# HelpDuinoShiled.net
KiCad netlist of a schematic drawn in EAGLE
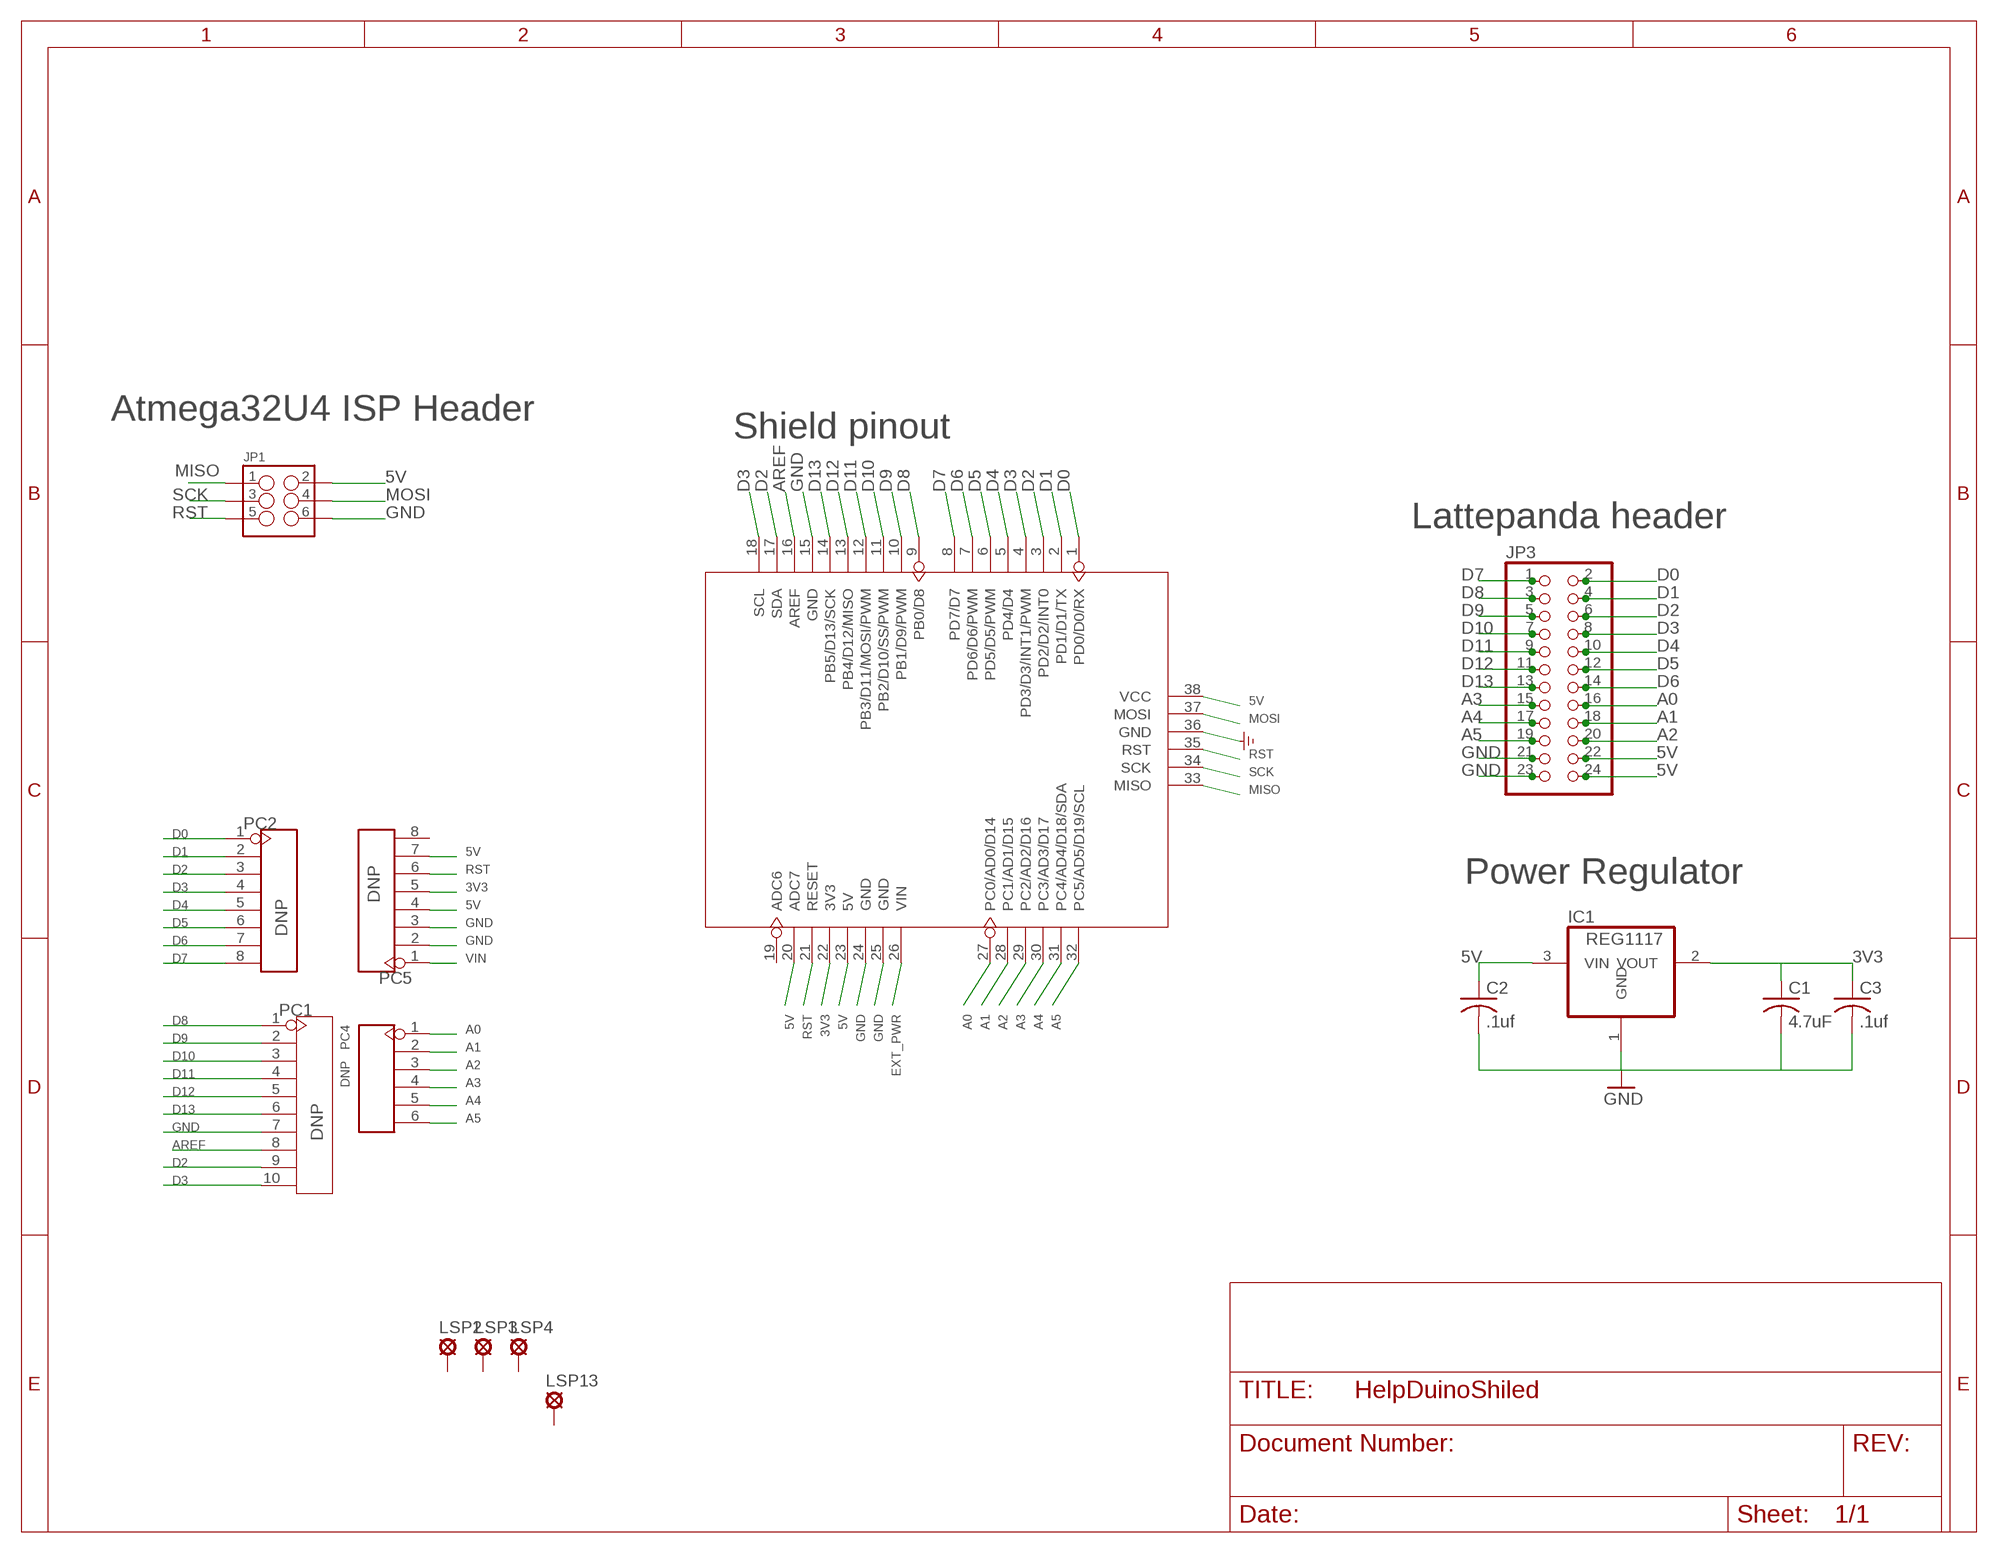
[diagram p0: schematic, sheet 1]

(export (version "E")
  (design (tool "Eeschema 10.0.6"))
  (components
    (comp (ref "C1")
      (value "4.7uF")
      (footprint "eagle-import:C0603K")
      (libsource (lib "eagle-import") (part "C-USC0603K"))
    )
    (comp (ref "C2")
      (value ".1uf")
      (footprint "eagle-import:C0603K")
      (libsource (lib "eagle-import") (part "C-USC0603K"))
    )
    (comp (ref "C3")
      (value ".1uf")
      (footprint "eagle-import:C0603K")
      (libsource (lib "eagle-import") (part "C-USC0603K"))
    )
    (comp (ref "IC1")
      (value "REG1117")
      (footprint "eagle-import:SOT223")
      (libsource (lib "eagle-import") (part "REG1117"))
    )
    (comp (ref "JP1")
      (value "M03X2NO_SILK")
      (footprint "eagle-import:2X3-NS")
      (libsource (lib "eagle-import") (part "M03X2NO_SILK"))
    )
    (comp (ref "JP3")
      (value "PINHD-2X12")
      (footprint "eagle-import:2X12")
      (libsource (lib "eagle-import") (part "PINHD-2X12"))
    )
    (comp (ref "LSP2")
      (value "SE13")
      (footprint "eagle-import:SE13")
      (libsource (lib "eagle-import") (part "SE13"))
    )
    (comp (ref "LSP3")
      (value "SE13")
      (footprint "eagle-import:SE13")
      (libsource (lib "eagle-import") (part "SE13"))
    )
    (comp (ref "LSP4")
      (value "SE13")
      (footprint "eagle-import:SE13")
      (libsource (lib "eagle-import") (part "SE13"))
    )
    (comp (ref "LSP13")
      (value "SE13")
      (footprint "eagle-import:SE13")
      (libsource (lib "eagle-import") (part "SE13"))
    )
    (comp (ref "PC1")
      (value "DNP")
      (footprint "eagle-import:10P-2.54")
      (libsource (lib "eagle-import") (part "HEADER-10P-2.54"))
    )
    (comp (ref "PC2")
      (value "DNP")
      (footprint "eagle-import:8P-2.54")
      (libsource (lib "eagle-import") (part "HEADER-8P-2.54"))
    )
    (comp (ref "PC4")
      (value "DNP")
      (footprint "eagle-import:6P-2.54-65_35MIL")
      (libsource (lib "eagle-import") (part "HEADER-6P-65/35MIL"))
    )
    (comp (ref "PC5")
      (value "DNP")
      (footprint "eagle-import:8P-2.54")
      (libsource (lib "eagle-import") (part "HEADER-8P-2.54"))
    )
    (comp (ref "U1")
      (value "ARDUINO-38PWITH/-SILK")
      (footprint "eagle-import:ARDUINO-38P-WITH_-SILK-500519002")
      (libsource (lib "eagle-import") (part "ARDUINO-38PWITH/-SILK"))
    )
  )
  (nets
    (net (code "1") (name "/3V3") (class "Default")
      (node (ref "C1") (pin "1") (pinfunction "1_1") (pintype "passive"))
      (node (ref "C3") (pin "1") (pinfunction "1_1") (pintype "passive"))
      (node (ref "IC1") (pin "2") (pinfunction "VOUT_2") (pintype "output"))
      (node (ref "PC5") (pin "5") (pinfunction "5_5") (pintype "bidirectional"))
      (node (ref "U1") (pin "22") (pinfunction "3V3_22") (pintype "bidirectional"))
    )
    (net (code "2") (name "/5V") (class "Default")
      (node (ref "C2") (pin "1") (pinfunction "1_1") (pintype "passive"))
      (node (ref "IC1") (pin "3") (pinfunction "VIN_3") (pintype "input"))
      (node (ref "JP1") (pin "2") (pinfunction "2_2") (pintype "bidirectional"))
      (node (ref "JP3") (pin "22") (pinfunction "22_22") (pintype "passive"))
      (node (ref "JP3") (pin "24") (pinfunction "24_24") (pintype "passive"))
      (node (ref "PC5") (pin "4") (pinfunction "4_4") (pintype "bidirectional"))
      (node (ref "PC5") (pin "7") (pinfunction "7_7") (pintype "bidirectional"))
      (node (ref "U1") (pin "20") (pinfunction "ADC7_20") (pintype "bidirectional"))
      (node (ref "U1") (pin "23") (pinfunction "5V_23") (pintype "bidirectional"))
      (node (ref "U1") (pin "38") (pinfunction "VCC_38") (pintype "bidirectional"))
    )
    (net (code "3") (name "/A0") (class "Default")
      (node (ref "JP3") (pin "16") (pinfunction "16_16") (pintype "passive"))
      (node (ref "PC4") (pin "1") (pinfunction "1_1") (pintype "bidirectional"))
      (node (ref "U1") (pin "27") (pinfunction "PC0/AD0/D14_27") (pintype "bidirectional"))
    )
    (net (code "4") (name "/A1") (class "Default")
      (node (ref "JP3") (pin "18") (pinfunction "18_18") (pintype "passive"))
      (node (ref "PC4") (pin "2") (pinfunction "2_2") (pintype "bidirectional"))
      (node (ref "U1") (pin "28") (pinfunction "PC1/AD1/D15_28") (pintype "bidirectional"))
    )
    (net (code "5") (name "/A2") (class "Default")
      (node (ref "JP3") (pin "20") (pinfunction "20_20") (pintype "passive"))
      (node (ref "PC4") (pin "3") (pinfunction "3_3") (pintype "bidirectional"))
      (node (ref "U1") (pin "29") (pinfunction "PC2/AD2/D16_29") (pintype "bidirectional"))
    )
    (net (code "6") (name "/A3") (class "Default")
      (node (ref "JP3") (pin "15") (pinfunction "15_15") (pintype "passive"))
      (node (ref "PC4") (pin "4") (pinfunction "4_4") (pintype "bidirectional"))
      (node (ref "U1") (pin "30") (pinfunction "PC3/AD3/D17_30") (pintype "bidirectional"))
    )
    (net (code "7") (name "/A4") (class "Default")
      (node (ref "JP3") (pin "17") (pinfunction "17_17") (pintype "passive"))
      (node (ref "PC4") (pin "5") (pinfunction "5_5") (pintype "bidirectional"))
      (node (ref "U1") (pin "31") (pinfunction "PC4/AD4/D18/SDA_31") (pintype "bidirectional"))
    )
    (net (code "8") (name "/A5") (class "Default")
      (node (ref "JP3") (pin "19") (pinfunction "19_19") (pintype "passive"))
      (node (ref "PC4") (pin "6") (pinfunction "6_6") (pintype "bidirectional"))
      (node (ref "U1") (pin "32") (pinfunction "PC5/AD5/D19/SCL_32") (pintype "bidirectional"))
    )
    (net (code "9") (name "/AREF") (class "Default")
      (node (ref "PC1") (pin "8") (pinfunction "8_8") (pintype "bidirectional"))
      (node (ref "U1") (pin "16") (pinfunction "AREF_16") (pintype "bidirectional"))
    )
    (net (code "10") (name "/D0") (class "Default")
      (node (ref "JP3") (pin "2") (pinfunction "2_2") (pintype "passive"))
      (node (ref "PC2") (pin "1") (pinfunction "1_1") (pintype "bidirectional"))
      (node (ref "U1") (pin "1") (pinfunction "PD0/D0/RX_1") (pintype "bidirectional"))
    )
    (net (code "11") (name "/D1") (class "Default")
      (node (ref "JP3") (pin "4") (pinfunction "4_4") (pintype "passive"))
      (node (ref "PC2") (pin "2") (pinfunction "2_2") (pintype "bidirectional"))
      (node (ref "U1") (pin "2") (pinfunction "PD1/D1/TX_2") (pintype "bidirectional"))
    )
    (net (code "12") (name "/D2") (class "Default")
      (node (ref "JP3") (pin "6") (pinfunction "6_6") (pintype "passive"))
      (node (ref "PC1") (pin "9") (pinfunction "9_9") (pintype "bidirectional"))
      (node (ref "PC2") (pin "3") (pinfunction "3_3") (pintype "bidirectional"))
      (node (ref "U1") (pin "17") (pinfunction "SDA_17") (pintype "bidirectional"))
      (node (ref "U1") (pin "3") (pinfunction "PD2/D2/INT0_3") (pintype "bidirectional"))
    )
    (net (code "13") (name "/D3") (class "Default")
      (node (ref "JP3") (pin "8") (pinfunction "8_8") (pintype "passive"))
      (node (ref "PC1") (pin "10") (pinfunction "10_10") (pintype "bidirectional"))
      (node (ref "PC2") (pin "4") (pinfunction "4_4") (pintype "bidirectional"))
      (node (ref "U1") (pin "18") (pinfunction "SCL_18") (pintype "bidirectional"))
      (node (ref "U1") (pin "4") (pinfunction "PD3/D3/INT1/PWM_4") (pintype "bidirectional"))
    )
    (net (code "14") (name "/D4") (class "Default")
      (node (ref "JP3") (pin "10") (pinfunction "10_10") (pintype "passive"))
      (node (ref "PC2") (pin "5") (pinfunction "5_5") (pintype "bidirectional"))
      (node (ref "U1") (pin "5") (pinfunction "PD4/D4_5") (pintype "bidirectional"))
    )
    (net (code "15") (name "/D5") (class "Default")
      (node (ref "JP3") (pin "12") (pinfunction "12_12") (pintype "passive"))
      (node (ref "PC2") (pin "6") (pinfunction "6_6") (pintype "bidirectional"))
      (node (ref "U1") (pin "6") (pinfunction "PD5/D5/PWM_6") (pintype "bidirectional"))
    )
    (net (code "16") (name "/D6") (class "Default")
      (node (ref "JP3") (pin "14") (pinfunction "14_14") (pintype "passive"))
      (node (ref "PC2") (pin "7") (pinfunction "7_7") (pintype "bidirectional"))
      (node (ref "U1") (pin "7") (pinfunction "PD6/D6/PWM_7") (pintype "bidirectional"))
    )
    (net (code "17") (name "/D7") (class "Default")
      (node (ref "JP3") (pin "1") (pinfunction "1_1") (pintype "passive"))
      (node (ref "PC2") (pin "8") (pinfunction "8_8") (pintype "bidirectional"))
      (node (ref "U1") (pin "8") (pinfunction "PD7/D7_8") (pintype "bidirectional"))
    )
    (net (code "18") (name "/D8") (class "Default")
      (node (ref "JP3") (pin "3") (pinfunction "3_3") (pintype "passive"))
      (node (ref "PC1") (pin "1") (pinfunction "1_1") (pintype "bidirectional"))
      (node (ref "U1") (pin "9") (pinfunction "PB0/D8_9") (pintype "bidirectional"))
    )
    (net (code "19") (name "/D9") (class "Default")
      (node (ref "JP3") (pin "5") (pinfunction "5_5") (pintype "passive"))
      (node (ref "PC1") (pin "2") (pinfunction "2_2") (pintype "bidirectional"))
      (node (ref "U1") (pin "10") (pinfunction "PB1/D9/PWM_10") (pintype "bidirectional"))
    )
    (net (code "20") (name "/D10") (class "Default")
      (node (ref "JP3") (pin "7") (pinfunction "7_7") (pintype "passive"))
      (node (ref "PC1") (pin "3") (pinfunction "3_3") (pintype "bidirectional"))
      (node (ref "U1") (pin "11") (pinfunction "PB2/D10/SS/PWM_11") (pintype "bidirectional"))
    )
    (net (code "21") (name "/D11") (class "Default")
      (node (ref "JP3") (pin "9") (pinfunction "9_9") (pintype "passive"))
      (node (ref "PC1") (pin "4") (pinfunction "4_4") (pintype "bidirectional"))
      (node (ref "U1") (pin "12") (pinfunction "PB3/D11/MOSI/PWM_12") (pintype "bidirectional"))
    )
    (net (code "22") (name "/D12") (class "Default")
      (node (ref "JP3") (pin "11") (pinfunction "11_11") (pintype "passive"))
      (node (ref "PC1") (pin "5") (pinfunction "5_5") (pintype "bidirectional"))
      (node (ref "U1") (pin "13") (pinfunction "PB4/D12/MISO_13") (pintype "bidirectional"))
    )
    (net (code "23") (name "/D13") (class "Default")
      (node (ref "JP3") (pin "13") (pinfunction "13_13") (pintype "passive"))
      (node (ref "PC1") (pin "6") (pinfunction "6_6") (pintype "bidirectional"))
      (node (ref "U1") (pin "14") (pinfunction "PB5/D13/SCK_14") (pintype "bidirectional"))
    )
    (net (code "24") (name "/EXT_PWR") (class "Default")
      (node (ref "U1") (pin "26") (pinfunction "VIN_26") (pintype "bidirectional"))
    )
    (net (code "25") (name "/MISO") (class "Default")
      (node (ref "JP1") (pin "1") (pinfunction "1_1") (pintype "bidirectional"))
      (node (ref "U1") (pin "33") (pinfunction "MISO_33") (pintype "bidirectional"))
    )
    (net (code "26") (name "/MOSI") (class "Default")
      (node (ref "JP1") (pin "4") (pinfunction "4_4") (pintype "bidirectional"))
      (node (ref "U1") (pin "37") (pinfunction "MOSI_37") (pintype "bidirectional"))
    )
    (net (code "27") (name "/RST") (class "Default")
      (node (ref "JP1") (pin "5") (pinfunction "5_5") (pintype "bidirectional"))
      (node (ref "PC5") (pin "6") (pinfunction "6_6") (pintype "bidirectional"))
      (node (ref "U1") (pin "21") (pinfunction "RESET_21") (pintype "bidirectional"))
      (node (ref "U1") (pin "35") (pinfunction "RST_35") (pintype "bidirectional"))
    )
    (net (code "28") (name "/SCK") (class "Default")
      (node (ref "JP1") (pin "3") (pinfunction "3_3") (pintype "bidirectional"))
      (node (ref "U1") (pin "34") (pinfunction "SCK_34") (pintype "bidirectional"))
    )
    (net (code "29") (name "/VIN") (class "Default")
      (node (ref "PC5") (pin "1") (pinfunction "1_1") (pintype "bidirectional"))
    )
    (net (code "30") (name "GND") (class "Default")
      (node (ref "C1") (pin "2") (pinfunction "2_2") (pintype "passive"))
      (node (ref "C2") (pin "2") (pinfunction "2_2") (pintype "passive"))
      (node (ref "C3") (pin "2") (pinfunction "2_2") (pintype "passive"))
      (node (ref "IC1") (pin "1") (pinfunction "GND_1") (pintype "power_in"))
      (node (ref "JP1") (pin "6") (pinfunction "6_6") (pintype "bidirectional"))
      (node (ref "JP3") (pin "21") (pinfunction "21_21") (pintype "passive"))
      (node (ref "JP3") (pin "23") (pinfunction "23_23") (pintype "passive"))
      (node (ref "PC1") (pin "7") (pinfunction "7_7") (pintype "bidirectional"))
      (node (ref "PC5") (pin "2") (pinfunction "2_2") (pintype "bidirectional"))
      (node (ref "PC5") (pin "3") (pinfunction "3_3") (pintype "bidirectional"))
      (node (ref "U1") (pin "15") (pinfunction "GND_15") (pintype "bidirectional"))
      (node (ref "U1") (pin "24") (pinfunction "GND_24") (pintype "bidirectional"))
      (node (ref "U1") (pin "25") (pinfunction "GND_25") (pintype "bidirectional"))
      (node (ref "U1") (pin "36") (pinfunction "GND_36") (pintype "bidirectional"))
    )
    (net (code "31") (name "unconnected-(LSP2-PadMP)") (class "Default")
      (node (ref "LSP2") (pin "MP") (pinfunction "MP_MP") (pintype "passive"))
    )
    (net (code "32") (name "unconnected-(LSP3-PadMP)") (class "Default")
      (node (ref "LSP3") (pin "MP") (pinfunction "MP_MP") (pintype "passive"))
    )
    (net (code "33") (name "unconnected-(LSP4-PadMP)") (class "Default")
      (node (ref "LSP4") (pin "MP") (pinfunction "MP_MP") (pintype "passive"))
    )
    (net (code "34") (name "unconnected-(LSP13-PadMP)") (class "Default")
      (node (ref "LSP13") (pin "MP") (pinfunction "MP_MP") (pintype "passive"))
    )
    (net (code "35") (name "unconnected-(PC5-Pad8)") (class "Default")
      (node (ref "PC5") (pin "8") (pinfunction "8_8") (pintype "bidirectional"))
    )
    (net (code "36") (name "unconnected-(U1-ADC6-Pad19)") (class "Default")
      (node (ref "U1") (pin "19") (pinfunction "ADC6_19") (pintype "bidirectional"))
    )
  )
)
